# Power.net
KiCad netlist of a schematic drawn in Altium Designer
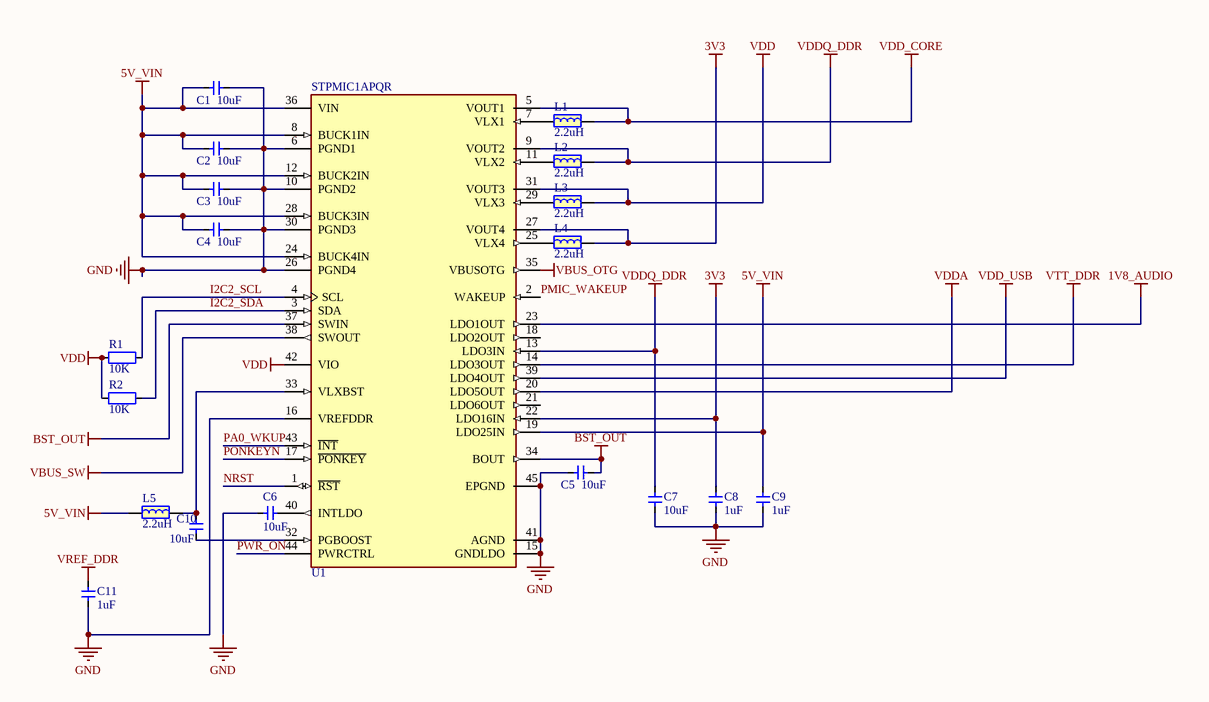
[diagram p0: Power.SchDoc]

(export (version "E")
  (design (tool "Eeschema 10.0.6"))
  (components
    (comp (ref "C1")
      (value "10uF")
      (footprint "CAP_0402")
      (description "Capacitor")
      (libsource (lib "MyPcbLib") (part "电容-0402"))
    )
    (comp (ref "C2")
      (value "10uF")
      (footprint "CAP_0402")
      (description "Capacitor")
      (libsource (lib "MyPcbLib") (part "电容-0402"))
    )
    (comp (ref "C3")
      (value "10uF")
      (footprint "CAP_0402")
      (description "Capacitor")
      (libsource (lib "MyPcbLib") (part "电容-0402"))
    )
    (comp (ref "C4")
      (value "10uF")
      (footprint "CAP_0402")
      (description "Capacitor")
      (libsource (lib "MyPcbLib") (part "电容-0402"))
    )
    (comp (ref "C5")
      (value "10uF")
      (footprint "CAP_0402")
      (description "Capacitor")
      (libsource (lib "MyPcbLib") (part "电容-0402"))
    )
    (comp (ref "C6")
      (value "10uF")
      (footprint "CAP_0402")
      (description "Capacitor")
      (libsource (lib "MyPcbLib") (part "电容-0402"))
    )
    (comp (ref "C7")
      (value "10uF")
      (footprint "CAP_0402")
      (description "Capacitor")
      (libsource (lib "MyPcbLib") (part "电容-0402"))
    )
    (comp (ref "C8")
      (value "1uF")
      (footprint "CAP_0402")
      (description "Capacitor")
      (libsource (lib "MyPcbLib") (part "电容-0402"))
    )
    (comp (ref "C9")
      (value "1uF")
      (footprint "CAP_0402")
      (description "Capacitor")
      (libsource (lib "MyPcbLib") (part "电容-0402"))
    )
    (comp (ref "C10")
      (value "10uF")
      (footprint "CAP_0402")
      (description "Capacitor")
      (libsource (lib "MyPcbLib") (part "电容-0402"))
    )
    (comp (ref "C11")
      (value "1uF")
      (footprint "CAP_0402")
      (description "Capacitor")
      (libsource (lib "MyPcbLib") (part "电容-0402"))
    )
    (comp (ref "L1") (value "2.2uH") (footprint "IND-201612") (libsource (lib "mLib") (part "电感-201612")))
    (comp (ref "L2") (value "2.2uH") (footprint "IND-201612") (libsource (lib "mLib") (part "电感-201612")))
    (comp (ref "L3") (value "2.2uH") (footprint "IND-201612") (libsource (lib "mLib") (part "电感-201612")))
    (comp (ref "L4") (value "2.2uH") (footprint "IND-201612") (libsource (lib "mLib") (part "电感-201612")))
    (comp (ref "L5") (value "2.2uH") (footprint "IND-201612") (libsource (lib "mLib") (part "电感-201612")))
    (comp (ref "R1")
      (value "10K")
      (footprint "RES_0402")
      (description "Resistor")
      (libsource (lib "MyPcbLib") (part "电阻-0402"))
    )
    (comp (ref "R2")
      (value "10K")
      (footprint "RES_0402")
      (description "Resistor")
      (libsource (lib "MyPcbLib") (part "电阻-0402"))
    )
    (comp (ref "U1")
      (value "STPMIC1APQR")
      (footprint "STMicroelectronics_WFQFN44L_IPC_C")
      (libsource (lib "MyPcbLib") (part "STPMIC1APQR"))
    )
  )
  (nets
    (net (code "1") (name "/I2C2_SCL") (class "Default")
      (node (ref "R1") (pin "1") (pinfunction "1_1") (pintype "passive"))
      (node (ref "U1") (pin "4") (pinfunction "SCL_4") (pintype "input"))
    )
    (net (code "2") (name "/I2C2_SDA") (class "Default")
      (node (ref "R2") (pin "1") (pinfunction "1_1") (pintype "passive"))
      (node (ref "U1") (pin "3") (pinfunction "SDA_3") (pintype "input"))
    )
    (net (code "3") (name "/NRST") (class "Default")
      (node (ref "U1") (pin "1") (pinfunction "~{RST}_1") (pintype "bidirectional"))
    )
    (net (code "4") (name "/PA0_WKUP") (class "Default")
      (node (ref "U1") (pin "43") (pinfunction "~{INT}_43") (pintype "input"))
    )
    (net (code "5") (name "/PMIC_WAKEUP") (class "Default")
      (node (ref "U1") (pin "2") (pinfunction "WAKEUP_2") (pintype "input"))
    )
    (net (code "6") (name "/PONKEYN") (class "Default")
      (node (ref "U1") (pin "17") (pinfunction "~{PONKEY}_17") (pintype "input"))
    )
    (net (code "7") (name "/PWR_ON") (class "Default")
      (node (ref "U1") (pin "44") (pinfunction "PWRCTRL_44") (pintype "power_in"))
    )
    (net (code "8") (name "1V8_AUDIO") (class "Default")
      (node (ref "U1") (pin "23") (pinfunction "LDO1OUT_23") (pintype "output"))
    )
    (net (code "9") (name "3V3") (class "Default")
      (node (ref "C8") (pin "2") (pinfunction "2_2") (pintype "passive"))
      (node (ref "L4") (pin "2") (pinfunction "2_2") (pintype "passive"))
      (node (ref "U1") (pin "22") (pinfunction "LDO16IN_22") (pintype "input"))
      (node (ref "U1") (pin "27") (pinfunction "VOUT4_27") (pintype "power_in"))
    )
    (net (code "10") (name "5V_VIN") (class "Default")
      (node (ref "C1") (pin "1") (pinfunction "1_1") (pintype "passive"))
      (node (ref "C2") (pin "1") (pinfunction "1_1") (pintype "passive"))
      (node (ref "C3") (pin "1") (pinfunction "1_1") (pintype "passive"))
      (node (ref "C4") (pin "1") (pinfunction "1_1") (pintype "passive"))
      (node (ref "C9") (pin "2") (pinfunction "2_2") (pintype "passive"))
      (node (ref "L5") (pin "1") (pintype "passive"))
      (node (ref "U1") (pin "12") (pinfunction "BUCK2IN_12") (pintype "input"))
      (node (ref "U1") (pin "19") (pinfunction "LDO25IN_19") (pintype "output"))
      (node (ref "U1") (pin "24") (pinfunction "BUCK4IN_24") (pintype "input"))
      (node (ref "U1") (pin "28") (pinfunction "BUCK3IN_28") (pintype "input"))
      (node (ref "U1") (pin "36") (pinfunction "VIN_36") (pintype "power_in"))
      (node (ref "U1") (pin "8") (pinfunction "BUCK1IN_8") (pintype "input"))
    )
    (net (code "11") (name "BST_OUT") (class "Default")
      (node (ref "C5") (pin "2") (pinfunction "2_2") (pintype "passive"))
      (node (ref "U1") (pin "34") (pinfunction "BOUT_34") (pintype "output"))
      (node (ref "U1") (pin "37") (pinfunction "SWIN_37") (pintype "input"))
    )
    (net (code "12") (name "GND") (class "Default")
      (node (ref "C1") (pin "2") (pinfunction "2_2") (pintype "passive"))
      (node (ref "C11") (pin "1") (pinfunction "1_1") (pintype "passive"))
      (node (ref "C2") (pin "2") (pinfunction "2_2") (pintype "passive"))
      (node (ref "C3") (pin "2") (pinfunction "2_2") (pintype "passive"))
      (node (ref "C4") (pin "2") (pinfunction "2_2") (pintype "passive"))
      (node (ref "C5") (pin "1") (pinfunction "1_1") (pintype "passive"))
      (node (ref "C6") (pin "2") (pinfunction "2_2") (pintype "passive"))
      (node (ref "C7") (pin "1") (pinfunction "1_1") (pintype "passive"))
      (node (ref "C8") (pin "1") (pinfunction "1_1") (pintype "passive"))
      (node (ref "C9") (pin "1") (pinfunction "1_1") (pintype "passive"))
      (node (ref "U1") (pin "10") (pinfunction "PGND2_10") (pintype "power_in"))
      (node (ref "U1") (pin "15") (pinfunction "GNDLDO_15") (pintype "power_in"))
      (node (ref "U1") (pin "16") (pinfunction "VREFDDR_16") (pintype "power_in"))
      (node (ref "U1") (pin "26") (pinfunction "PGND4_26") (pintype "power_in"))
      (node (ref "U1") (pin "30") (pinfunction "PGND3_30") (pintype "power_in"))
      (node (ref "U1") (pin "41") (pinfunction "AGND_41") (pintype "power_in"))
      (node (ref "U1") (pin "45") (pinfunction "EPGND_45") (pintype "power_in"))
      (node (ref "U1") (pin "6") (pinfunction "PGND1_6") (pintype "power_in"))
    )
    (net (code "13") (name "Net-(U1-INTLDO)") (class "Default")
      (node (ref "C6") (pin "1") (pinfunction "1_1") (pintype "passive"))
      (node (ref "U1") (pin "40") (pinfunction "INTLDO_40") (pintype "output"))
    )
    (net (code "14") (name "Net-(U1-PGBOOST)") (class "Default")
      (node (ref "C10") (pin "1") (pinfunction "1_1") (pintype "passive"))
      (node (ref "U1") (pin "32") (pinfunction "PGBOOST_32") (pintype "input"))
    )
    (net (code "15") (name "Net-(U1-VLX1)") (class "Default")
      (node (ref "L1") (pin "1") (pintype "passive"))
      (node (ref "U1") (pin "7") (pinfunction "VLX1_7") (pintype "input"))
    )
    (net (code "16") (name "Net-(U1-VLX2)") (class "Default")
      (node (ref "L2") (pin "1") (pintype "passive"))
      (node (ref "U1") (pin "11") (pinfunction "VLX2_11") (pintype "input"))
    )
    (net (code "17") (name "Net-(U1-VLX3)") (class "Default")
      (node (ref "L3") (pin "1") (pintype "passive"))
      (node (ref "U1") (pin "29") (pinfunction "VLX3_29") (pintype "input"))
    )
    (net (code "18") (name "Net-(U1-VLX4)") (class "Default")
      (node (ref "L4") (pin "1") (pintype "passive"))
      (node (ref "U1") (pin "25") (pinfunction "VLX4_25") (pintype "output"))
    )
    (net (code "19") (name "Net-(U1-VLXBST)") (class "Default")
      (node (ref "C10") (pin "2") (pinfunction "2_2") (pintype "passive"))
      (node (ref "L5") (pin "2") (pinfunction "2_2") (pintype "passive"))
      (node (ref "U1") (pin "33") (pinfunction "VLXBST_33") (pintype "input"))
    )
    (net (code "20") (name "VBUS_OTG") (class "Default")
      (node (ref "U1") (pin "35") (pinfunction "VBUSOTG_35") (pintype "output"))
    )
    (net (code "21") (name "VBUS_SW") (class "Default")
      (node (ref "U1") (pin "38") (pinfunction "SWOUT_38") (pintype "output"))
    )
    (net (code "22") (name "VDD") (class "Default")
      (node (ref "L3") (pin "2") (pinfunction "2_2") (pintype "passive"))
      (node (ref "R1") (pin "2") (pinfunction "2_2") (pintype "passive"))
      (node (ref "R2") (pin "2") (pinfunction "2_2") (pintype "passive"))
      (node (ref "U1") (pin "31") (pinfunction "VOUT3_31") (pintype "power_in"))
      (node (ref "U1") (pin "42") (pinfunction "VIO_42") (pintype "power_in"))
    )
    (net (code "23") (name "VDDA") (class "Default")
      (node (ref "U1") (pin "20") (pinfunction "LDO5OUT_20") (pintype "output"))
    )
    (net (code "24") (name "VDDQ_DDR") (class "Default")
      (node (ref "C7") (pin "2") (pinfunction "2_2") (pintype "passive"))
      (node (ref "L2") (pin "2") (pinfunction "2_2") (pintype "passive"))
      (node (ref "U1") (pin "13") (pinfunction "LDO3IN_13") (pintype "input"))
      (node (ref "U1") (pin "9") (pinfunction "VOUT2_9") (pintype "power_in"))
    )
    (net (code "25") (name "VDD_CORE") (class "Default")
      (node (ref "L1") (pin "2") (pinfunction "2_2") (pintype "passive"))
      (node (ref "U1") (pin "5") (pinfunction "VOUT1_5") (pintype "power_in"))
    )
    (net (code "26") (name "VDD_USB") (class "Default")
      (node (ref "U1") (pin "39") (pinfunction "LDO4OUT_39") (pintype "output"))
    )
    (net (code "27") (name "VREF_DDR") (class "Default")
      (node (ref "C11") (pin "2") (pinfunction "2_2") (pintype "passive"))
    )
    (net (code "28") (name "VTT_DDR") (class "Default")
      (node (ref "U1") (pin "14") (pinfunction "LDO3OUT_14") (pintype "output"))
    )
    (net (code "29") (name "unconnected-(U1-LDO2OUT-Pad18)") (class "Default")
      (node (ref "U1") (pin "18") (pinfunction "LDO2OUT_18") (pintype "output"))
    )
    (net (code "30") (name "unconnected-(U1-LDO6OUT-Pad21)") (class "Default")
      (node (ref "U1") (pin "21") (pinfunction "LDO6OUT_21") (pintype "output"))
    )
  )
)
